# fpga02-serdes-power.net
KiCad netlist of a schematic drawn in Altium Designer
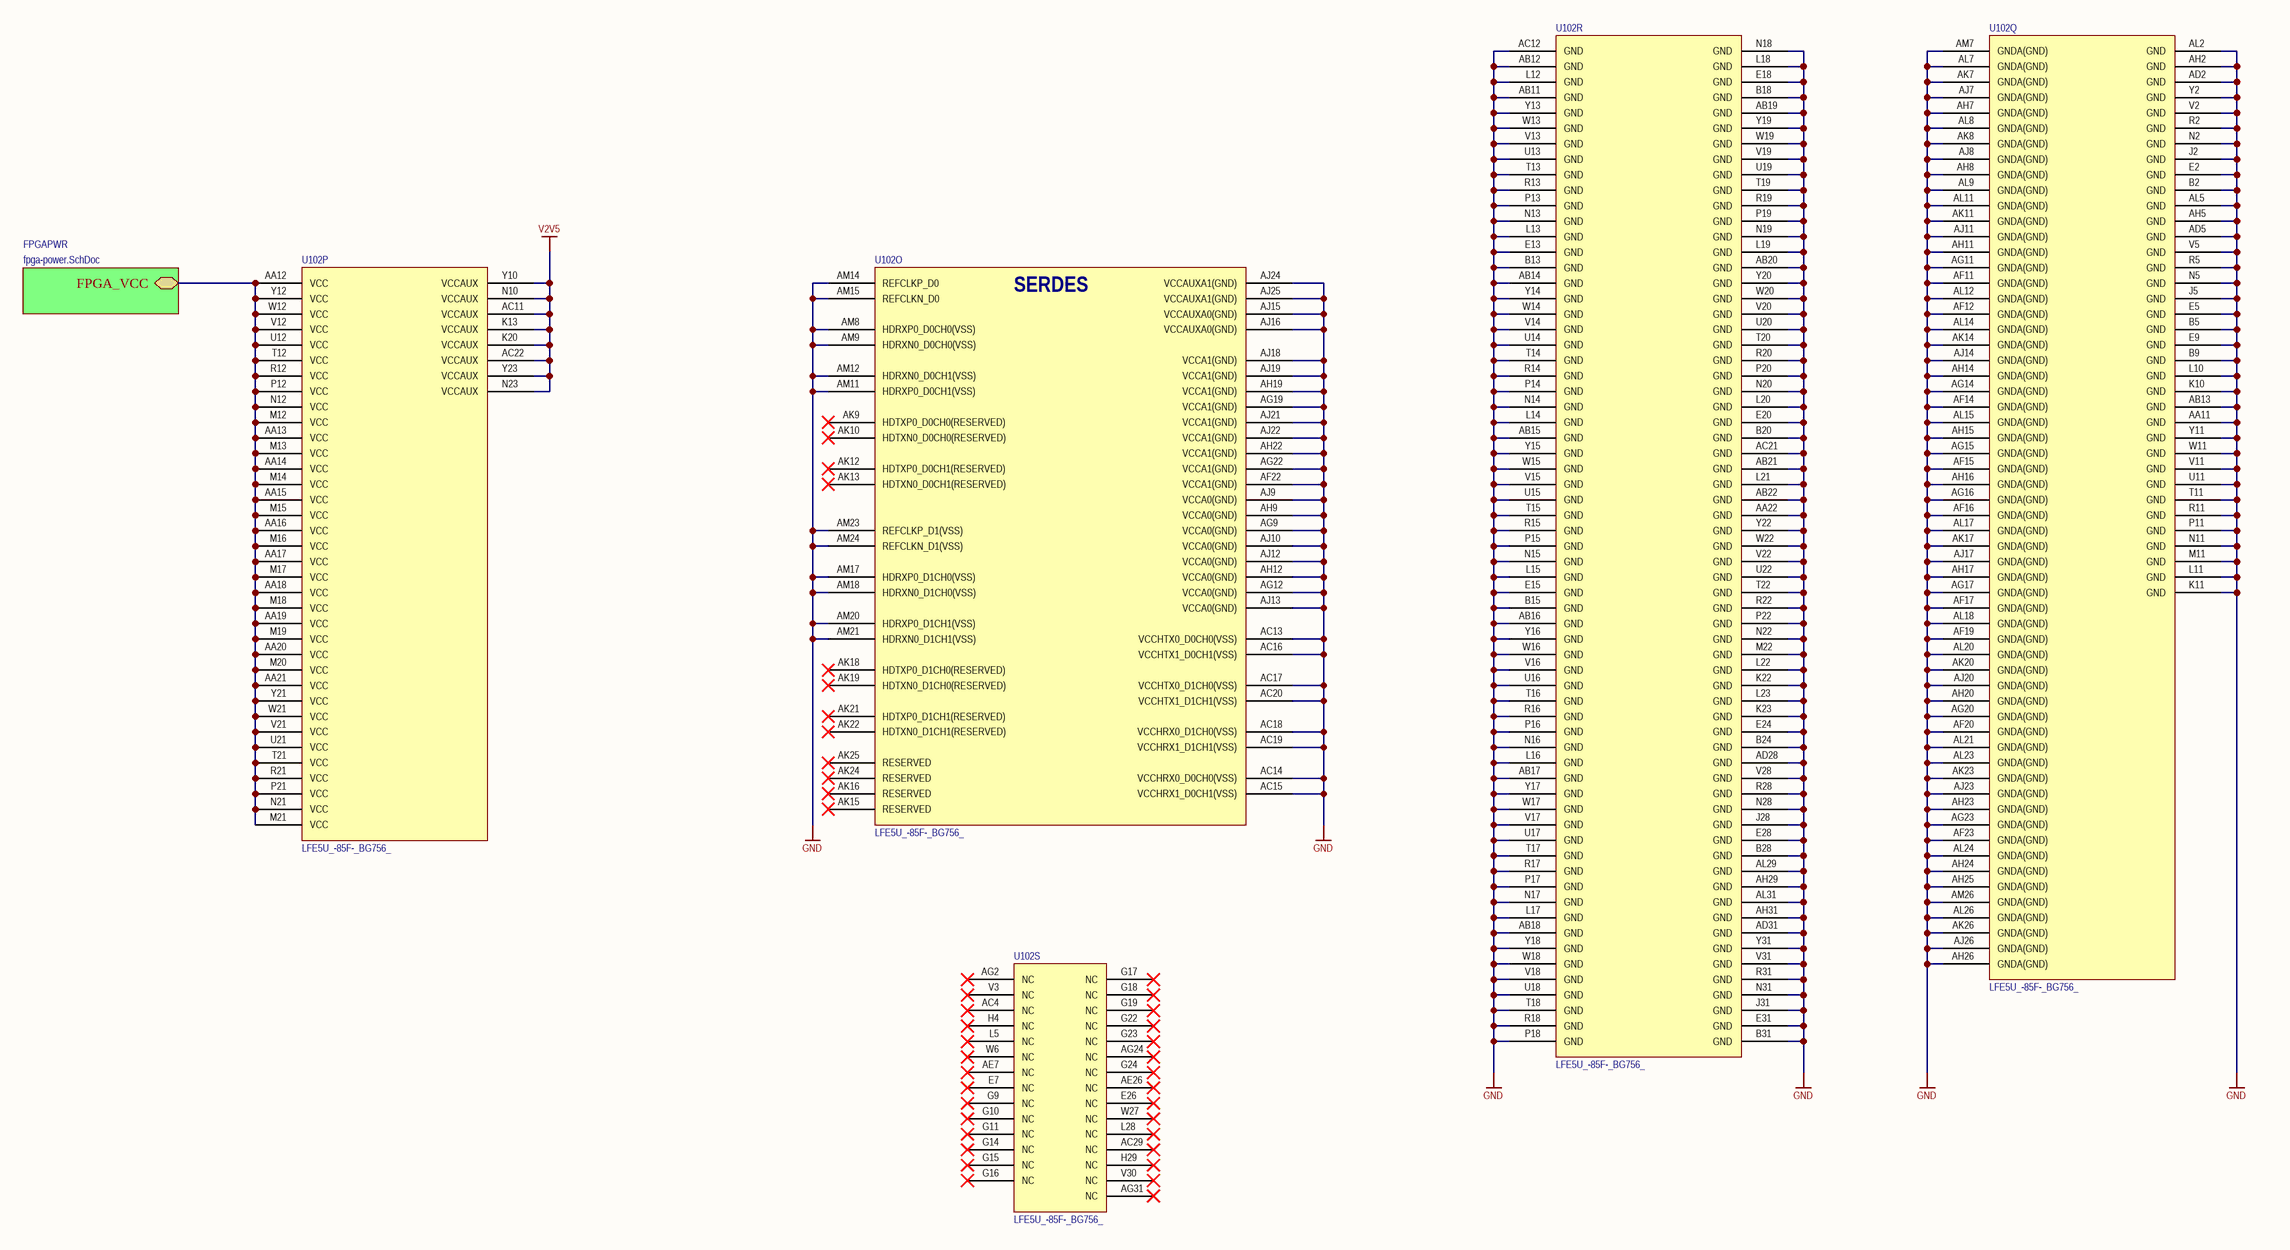
[diagram p0: fpga02-serdes-power.SchDoc]

(export (version "E")
  (design (tool "Eeschema 10.0.6"))
  (components
    (comp (ref "U102")
      (value "LFE5U_-85F-_BG756_")
      (footprint "lattice:caBGA756")
      (description "ECP5 FPGA, 85k LUT, 756-caBGA")
      (fields (field (name "MANUFACTURER") "Lattice Semiconductor"))
      (libsource (lib "lattice") (part "LFE5U_-85F-_BG756_"))
    )
  )
  (nets
    (net (code "1") (name "/FPGA_VCC") (class "Default")
      (node (ref "U102") (pin "AA12") (pinfunction "VCC_AA12") (pintype "power_in"))
      (node (ref "U102") (pin "AA13") (pinfunction "VCC_AA13") (pintype "power_in"))
      (node (ref "U102") (pin "AA14") (pinfunction "VCC_AA14") (pintype "power_in"))
      (node (ref "U102") (pin "AA15") (pinfunction "VCC_AA15") (pintype "power_in"))
      (node (ref "U102") (pin "AA16") (pinfunction "VCC_AA16") (pintype "power_in"))
      (node (ref "U102") (pin "AA17") (pinfunction "VCC_AA17") (pintype "power_in"))
      (node (ref "U102") (pin "AA18") (pinfunction "VCC_AA18") (pintype "power_in"))
      (node (ref "U102") (pin "AA19") (pinfunction "VCC_AA19") (pintype "power_in"))
      (node (ref "U102") (pin "AA20") (pinfunction "VCC_AA20") (pintype "power_in"))
      (node (ref "U102") (pin "AA21") (pinfunction "VCC_AA21") (pintype "power_in"))
      (node (ref "U102") (pin "M12") (pinfunction "VCC_M12") (pintype "power_in"))
      (node (ref "U102") (pin "M13") (pinfunction "VCC_M13") (pintype "power_in"))
      (node (ref "U102") (pin "M14") (pinfunction "VCC_M14") (pintype "power_in"))
      (node (ref "U102") (pin "M15") (pinfunction "VCC_M15") (pintype "power_in"))
      (node (ref "U102") (pin "M16") (pinfunction "VCC_M16") (pintype "power_in"))
      (node (ref "U102") (pin "M17") (pinfunction "VCC_M17") (pintype "power_in"))
      (node (ref "U102") (pin "M18") (pinfunction "VCC_M18") (pintype "power_in"))
      (node (ref "U102") (pin "M19") (pinfunction "VCC_M19") (pintype "power_in"))
      (node (ref "U102") (pin "M20") (pinfunction "VCC_M20") (pintype "power_in"))
      (node (ref "U102") (pin "M21") (pinfunction "VCC_M21") (pintype "power_in"))
      (node (ref "U102") (pin "N12") (pinfunction "VCC_N12") (pintype "power_in"))
      (node (ref "U102") (pin "N21") (pinfunction "VCC_N21") (pintype "power_in"))
      (node (ref "U102") (pin "P12") (pinfunction "VCC_P12") (pintype "power_in"))
      (node (ref "U102") (pin "P21") (pinfunction "VCC_P21") (pintype "power_in"))
      (node (ref "U102") (pin "R12") (pinfunction "VCC_R12") (pintype "power_in"))
      (node (ref "U102") (pin "R21") (pinfunction "VCC_R21") (pintype "power_in"))
      (node (ref "U102") (pin "T12") (pinfunction "VCC_T12") (pintype "power_in"))
      (node (ref "U102") (pin "T21") (pinfunction "VCC_T21") (pintype "power_in"))
      (node (ref "U102") (pin "U12") (pinfunction "VCC_U12") (pintype "power_in"))
      (node (ref "U102") (pin "U21") (pinfunction "VCC_U21") (pintype "power_in"))
      (node (ref "U102") (pin "V12") (pinfunction "VCC_V12") (pintype "power_in"))
      (node (ref "U102") (pin "V21") (pinfunction "VCC_V21") (pintype "power_in"))
      (node (ref "U102") (pin "W12") (pinfunction "VCC_W12") (pintype "power_in"))
      (node (ref "U102") (pin "W21") (pinfunction "VCC_W21") (pintype "power_in"))
      (node (ref "U102") (pin "Y12") (pinfunction "VCC_Y12") (pintype "power_in"))
      (node (ref "U102") (pin "Y21") (pinfunction "VCC_Y21") (pintype "power_in"))
    )
    (net (code "2") (name "GND") (class "Default")
      (node (ref "U102") (pin "AA11") (pinfunction "GND_AA11") (pintype "power_in"))
      (node (ref "U102") (pin "AA22") (pinfunction "GND_AA22") (pintype "power_in"))
      (node (ref "U102") (pin "AB11") (pinfunction "GND_AB11") (pintype "power_in"))
      (node (ref "U102") (pin "AB12") (pinfunction "GND_AB12") (pintype "power_in"))
      (node (ref "U102") (pin "AB13") (pinfunction "GND_AB13") (pintype "power_in"))
      (node (ref "U102") (pin "AB14") (pinfunction "GND_AB14") (pintype "power_in"))
      (node (ref "U102") (pin "AB15") (pinfunction "GND_AB15") (pintype "power_in"))
      (node (ref "U102") (pin "AB16") (pinfunction "GND_AB16") (pintype "power_in"))
      (node (ref "U102") (pin "AB17") (pinfunction "GND_AB17") (pintype "power_in"))
      (node (ref "U102") (pin "AB18") (pinfunction "GND_AB18") (pintype "power_in"))
      (node (ref "U102") (pin "AB19") (pinfunction "GND_AB19") (pintype "power_in"))
      (node (ref "U102") (pin "AB20") (pinfunction "GND_AB20") (pintype "power_in"))
      (node (ref "U102") (pin "AB21") (pinfunction "GND_AB21") (pintype "power_in"))
      (node (ref "U102") (pin "AB22") (pinfunction "GND_AB22") (pintype "power_in"))
      (node (ref "U102") (pin "AC12") (pinfunction "GND_AC12") (pintype "power_in"))
      (node (ref "U102") (pin "AC13") (pinfunction "VCCHTX0_D0CH0(VSS)_AC13") (pintype "power_in"))
      (node (ref "U102") (pin "AC14") (pinfunction "VCCHRX0_D0CH0(VSS)_AC14") (pintype "power_in"))
      (node (ref "U102") (pin "AC15") (pinfunction "VCCHRX1_D0CH1(VSS)_AC15") (pintype "power_in"))
      (node (ref "U102") (pin "AC16") (pinfunction "VCCHTX1_D0CH1(VSS)_AC16") (pintype "power_in"))
      (node (ref "U102") (pin "AC17") (pinfunction "VCCHTX0_D1CH0(VSS)_AC17") (pintype "power_in"))
      (node (ref "U102") (pin "AC18") (pinfunction "VCCHRX0_D1CH0(VSS)_AC18") (pintype "power_in"))
      (node (ref "U102") (pin "AC19") (pinfunction "VCCHRX1_D1CH1(VSS)_AC19") (pintype "power_in"))
      (node (ref "U102") (pin "AC20") (pinfunction "VCCHTX1_D1CH1(VSS)_AC20") (pintype "power_in"))
      (node (ref "U102") (pin "AC21") (pinfunction "GND_AC21") (pintype "power_in"))
      (node (ref "U102") (pin "AD2") (pinfunction "GND_AD2") (pintype "power_in"))
      (node (ref "U102") (pin "AD28") (pinfunction "GND_AD28") (pintype "power_in"))
      (node (ref "U102") (pin "AD31") (pinfunction "GND_AD31") (pintype "power_in"))
      (node (ref "U102") (pin "AD5") (pinfunction "GND_AD5") (pintype "power_in"))
      (node (ref "U102") (pin "AF11") (pinfunction "GNDA(GND)_AF11") (pintype "power_in"))
      (node (ref "U102") (pin "AF12") (pinfunction "GNDA(GND)_AF12") (pintype "power_in"))
      (node (ref "U102") (pin "AF14") (pinfunction "GNDA(GND)_AF14") (pintype "power_in"))
      (node (ref "U102") (pin "AF15") (pinfunction "GNDA(GND)_AF15") (pintype "power_in"))
      (node (ref "U102") (pin "AF16") (pinfunction "GNDA(GND)_AF16") (pintype "power_in"))
      (node (ref "U102") (pin "AF17") (pinfunction "GNDA(GND)_AF17") (pintype "power_in"))
      (node (ref "U102") (pin "AF19") (pinfunction "GNDA(GND)_AF19") (pintype "power_in"))
      (node (ref "U102") (pin "AF20") (pinfunction "GNDA(GND)_AF20") (pintype "power_in"))
      (node (ref "U102") (pin "AF22") (pinfunction "VCCA1(GND)_AF22") (pintype "power_in"))
      (node (ref "U102") (pin "AF23") (pinfunction "GNDA(GND)_AF23") (pintype "power_in"))
      (node (ref "U102") (pin "AG11") (pinfunction "GNDA(GND)_AG11") (pintype "power_in"))
      (node (ref "U102") (pin "AG12") (pinfunction "VCCA0(GND)_AG12") (pintype "power_in"))
      (node (ref "U102") (pin "AG14") (pinfunction "GNDA(GND)_AG14") (pintype "power_in"))
      (node (ref "U102") (pin "AG15") (pinfunction "GNDA(GND)_AG15") (pintype "power_in"))
      (node (ref "U102") (pin "AG16") (pinfunction "GNDA(GND)_AG16") (pintype "power_in"))
      (node (ref "U102") (pin "AG17") (pinfunction "GNDA(GND)_AG17") (pintype "power_in"))
      (node (ref "U102") (pin "AG19") (pinfunction "VCCA1(GND)_AG19") (pintype "power_in"))
      (node (ref "U102") (pin "AG20") (pinfunction "GNDA(GND)_AG20") (pintype "power_in"))
      (node (ref "U102") (pin "AG22") (pinfunction "VCCA1(GND)_AG22") (pintype "power_in"))
      (node (ref "U102") (pin "AG23") (pinfunction "GNDA(GND)_AG23") (pintype "power_in"))
      (node (ref "U102") (pin "AG9") (pinfunction "VCCA0(GND)_AG9") (pintype "power_in"))
      (node (ref "U102") (pin "AH11") (pinfunction "GNDA(GND)_AH11") (pintype "power_in"))
      (node (ref "U102") (pin "AH12") (pinfunction "VCCA0(GND)_AH12") (pintype "power_in"))
      (node (ref "U102") (pin "AH14") (pinfunction "GNDA(GND)_AH14") (pintype "power_in"))
      (node (ref "U102") (pin "AH15") (pinfunction "GNDA(GND)_AH15") (pintype "power_in"))
      (node (ref "U102") (pin "AH16") (pinfunction "GNDA(GND)_AH16") (pintype "power_in"))
      (node (ref "U102") (pin "AH17") (pinfunction "GNDA(GND)_AH17") (pintype "power_in"))
      (node (ref "U102") (pin "AH19") (pinfunction "VCCA1(GND)_AH19") (pintype "power_in"))
      (node (ref "U102") (pin "AH2") (pinfunction "GND_AH2") (pintype "power_in"))
      (node (ref "U102") (pin "AH20") (pinfunction "GNDA(GND)_AH20") (pintype "power_in"))
      (node (ref "U102") (pin "AH22") (pinfunction "VCCA1(GND)_AH22") (pintype "power_in"))
      (node (ref "U102") (pin "AH23") (pinfunction "GNDA(GND)_AH23") (pintype "power_in"))
      (node (ref "U102") (pin "AH24") (pinfunction "GNDA(GND)_AH24") (pintype "power_in"))
      (node (ref "U102") (pin "AH25") (pinfunction "GNDA(GND)_AH25") (pintype "power_in"))
      (node (ref "U102") (pin "AH26") (pinfunction "GNDA(GND)_AH26") (pintype "power_in"))
      (node (ref "U102") (pin "AH29") (pinfunction "GND_AH29") (pintype "power_in"))
      (node (ref "U102") (pin "AH31") (pinfunction "GND_AH31") (pintype "power_in"))
      (node (ref "U102") (pin "AH5") (pinfunction "GND_AH5") (pintype "power_in"))
      (node (ref "U102") (pin "AH7") (pinfunction "GNDA(GND)_AH7") (pintype "power_in"))
      (node (ref "U102") (pin "AH8") (pinfunction "GNDA(GND)_AH8") (pintype "power_in"))
      (node (ref "U102") (pin "AH9") (pinfunction "VCCA0(GND)_AH9") (pintype "power_in"))
      (node (ref "U102") (pin "AJ10") (pinfunction "VCCA0(GND)_AJ10") (pintype "power_in"))
      (node (ref "U102") (pin "AJ11") (pinfunction "GNDA(GND)_AJ11") (pintype "power_in"))
      (node (ref "U102") (pin "AJ12") (pinfunction "VCCA0(GND)_AJ12") (pintype "power_in"))
      (node (ref "U102") (pin "AJ13") (pinfunction "VCCA0(GND)_AJ13") (pintype "power_in"))
      (node (ref "U102") (pin "AJ14") (pinfunction "GNDA(GND)_AJ14") (pintype "power_in"))
      (node (ref "U102") (pin "AJ15") (pinfunction "VCCAUXA0(GND)_AJ15") (pintype "power_in"))
      (node (ref "U102") (pin "AJ16") (pinfunction "VCCAUXA0(GND)_AJ16") (pintype "power_in"))
      (node (ref "U102") (pin "AJ17") (pinfunction "GNDA(GND)_AJ17") (pintype "power_in"))
      (node (ref "U102") (pin "AJ18") (pinfunction "VCCA1(GND)_AJ18") (pintype "power_in"))
      (node (ref "U102") (pin "AJ19") (pinfunction "VCCA1(GND)_AJ19") (pintype "power_in"))
      (node (ref "U102") (pin "AJ20") (pinfunction "GNDA(GND)_AJ20") (pintype "power_in"))
      (node (ref "U102") (pin "AJ21") (pinfunction "VCCA1(GND)_AJ21") (pintype "power_in"))
      (node (ref "U102") (pin "AJ22") (pinfunction "VCCA1(GND)_AJ22") (pintype "power_in"))
      (node (ref "U102") (pin "AJ23") (pinfunction "GNDA(GND)_AJ23") (pintype "power_in"))
      (node (ref "U102") (pin "AJ24") (pinfunction "VCCAUXA1(GND)_AJ24") (pintype "power_in"))
      (node (ref "U102") (pin "AJ25") (pinfunction "VCCAUXA1(GND)_AJ25") (pintype "power_in"))
      (node (ref "U102") (pin "AJ26") (pinfunction "GNDA(GND)_AJ26") (pintype "power_in"))
      (node (ref "U102") (pin "AJ7") (pinfunction "GNDA(GND)_AJ7") (pintype "power_in"))
      (node (ref "U102") (pin "AJ8") (pinfunction "GNDA(GND)_AJ8") (pintype "power_in"))
      (node (ref "U102") (pin "AJ9") (pinfunction "VCCA0(GND)_AJ9") (pintype "power_in"))
      (node (ref "U102") (pin "AK11") (pinfunction "GNDA(GND)_AK11") (pintype "power_in"))
      (node (ref "U102") (pin "AK14") (pinfunction "GNDA(GND)_AK14") (pintype "power_in"))
      (node (ref "U102") (pin "AK17") (pinfunction "GNDA(GND)_AK17") (pintype "power_in"))
      (node (ref "U102") (pin "AK20") (pinfunction "GNDA(GND)_AK20") (pintype "power_in"))
      (node (ref "U102") (pin "AK23") (pinfunction "GNDA(GND)_AK23") (pintype "power_in"))
      (node (ref "U102") (pin "AK26") (pinfunction "GNDA(GND)_AK26") (pintype "power_in"))
      (node (ref "U102") (pin "AK7") (pinfunction "GNDA(GND)_AK7") (pintype "power_in"))
      (node (ref "U102") (pin "AK8") (pinfunction "GNDA(GND)_AK8") (pintype "power_in"))
      (node (ref "U102") (pin "AL11") (pinfunction "GNDA(GND)_AL11") (pintype "power_in"))
      (node (ref "U102") (pin "AL12") (pinfunction "GNDA(GND)_AL12") (pintype "power_in"))
      (node (ref "U102") (pin "AL14") (pinfunction "GNDA(GND)_AL14") (pintype "power_in"))
      (node (ref "U102") (pin "AL15") (pinfunction "GNDA(GND)_AL15") (pintype "power_in"))
      (node (ref "U102") (pin "AL17") (pinfunction "GNDA(GND)_AL17") (pintype "power_in"))
      (node (ref "U102") (pin "AL18") (pinfunction "GNDA(GND)_AL18") (pintype "power_in"))
      (node (ref "U102") (pin "AL2") (pinfunction "GND_AL2") (pintype "power_in"))
      (node (ref "U102") (pin "AL20") (pinfunction "GNDA(GND)_AL20") (pintype "power_in"))
      (node (ref "U102") (pin "AL21") (pinfunction "GNDA(GND)_AL21") (pintype "power_in"))
      (node (ref "U102") (pin "AL23") (pinfunction "GNDA(GND)_AL23") (pintype "power_in"))
      (node (ref "U102") (pin "AL24") (pinfunction "GNDA(GND)_AL24") (pintype "power_in"))
      (node (ref "U102") (pin "AL26") (pinfunction "GNDA(GND)_AL26") (pintype "power_in"))
      (node (ref "U102") (pin "AL29") (pinfunction "GND_AL29") (pintype "power_in"))
      (node (ref "U102") (pin "AL31") (pinfunction "GND_AL31") (pintype "power_in"))
      (node (ref "U102") (pin "AL5") (pinfunction "GND_AL5") (pintype "power_in"))
      (node (ref "U102") (pin "AL7") (pinfunction "GNDA(GND)_AL7") (pintype "power_in"))
      (node (ref "U102") (pin "AL8") (pinfunction "GNDA(GND)_AL8") (pintype "power_in"))
      (node (ref "U102") (pin "AL9") (pinfunction "GNDA(GND)_AL9") (pintype "power_in"))
      (node (ref "U102") (pin "AM11") (pinfunction "HDRXP0_D0CH1(VSS)_AM11") (pintype "passive"))
      (node (ref "U102") (pin "AM12") (pinfunction "HDRXN0_D0CH1(VSS)_AM12") (pintype "passive"))
      (node (ref "U102") (pin "AM14") (pinfunction "REFCLKP_D0_AM14") (pintype "passive"))
      (node (ref "U102") (pin "AM15") (pinfunction "REFCLKN_D0_AM15") (pintype "passive"))
      (node (ref "U102") (pin "AM17") (pinfunction "HDRXP0_D1CH0(VSS)_AM17") (pintype "passive"))
      (node (ref "U102") (pin "AM18") (pinfunction "HDRXN0_D1CH0(VSS)_AM18") (pintype "passive"))
      (node (ref "U102") (pin "AM20") (pinfunction "HDRXP0_D1CH1(VSS)_AM20") (pintype "passive"))
      (node (ref "U102") (pin "AM21") (pinfunction "HDRXN0_D1CH1(VSS)_AM21") (pintype "passive"))
      (node (ref "U102") (pin "AM23") (pinfunction "REFCLKP_D1(VSS)_AM23") (pintype "passive"))
      (node (ref "U102") (pin "AM24") (pinfunction "REFCLKN_D1(VSS)_AM24") (pintype "passive"))
      (node (ref "U102") (pin "AM26") (pinfunction "GNDA(GND)_AM26") (pintype "power_in"))
      (node (ref "U102") (pin "AM7") (pinfunction "GNDA(GND)_AM7") (pintype "power_in"))
      (node (ref "U102") (pin "AM8") (pinfunction "HDRXP0_D0CH0(VSS)_AM8") (pintype "passive"))
      (node (ref "U102") (pin "AM9") (pinfunction "HDRXN0_D0CH0(VSS)_AM9") (pintype "passive"))
      (node (ref "U102") (pin "B13") (pinfunction "GND_B13") (pintype "power_in"))
      (node (ref "U102") (pin "B15") (pinfunction "GND_B15") (pintype "power_in"))
      (node (ref "U102") (pin "B18") (pinfunction "GND_B18") (pintype "power_in"))
      (node (ref "U102") (pin "B2") (pinfunction "GND_B2") (pintype "power_in"))
      (node (ref "U102") (pin "B20") (pinfunction "GND_B20") (pintype "power_in"))
      (node (ref "U102") (pin "B24") (pinfunction "GND_B24") (pintype "power_in"))
      (node (ref "U102") (pin "B28") (pinfunction "GND_B28") (pintype "power_in"))
      (node (ref "U102") (pin "B31") (pinfunction "GND_B31") (pintype "power_in"))
      (node (ref "U102") (pin "B5") (pinfunction "GND_B5") (pintype "power_in"))
      (node (ref "U102") (pin "B9") (pinfunction "GND_B9") (pintype "power_in"))
      (node (ref "U102") (pin "E13") (pinfunction "GND_E13") (pintype "power_in"))
      (node (ref "U102") (pin "E15") (pinfunction "GND_E15") (pintype "power_in"))
      (node (ref "U102") (pin "E18") (pinfunction "GND_E18") (pintype "power_in"))
      (node (ref "U102") (pin "E2") (pinfunction "GND_E2") (pintype "power_in"))
      (node (ref "U102") (pin "E20") (pinfunction "GND_E20") (pintype "power_in"))
      (node (ref "U102") (pin "E24") (pinfunction "GND_E24") (pintype "power_in"))
      (node (ref "U102") (pin "E28") (pinfunction "GND_E28") (pintype "power_in"))
      (node (ref "U102") (pin "E31") (pinfunction "GND_E31") (pintype "power_in"))
      (node (ref "U102") (pin "E5") (pinfunction "GND_E5") (pintype "power_in"))
      (node (ref "U102") (pin "E9") (pinfunction "GND_E9") (pintype "power_in"))
      (node (ref "U102") (pin "J2") (pinfunction "GND_J2") (pintype "power_in"))
      (node (ref "U102") (pin "J28") (pinfunction "GND_J28") (pintype "power_in"))
      (node (ref "U102") (pin "J31") (pinfunction "GND_J31") (pintype "power_in"))
      (node (ref "U102") (pin "J5") (pinfunction "GND_J5") (pintype "power_in"))
      (node (ref "U102") (pin "K10") (pinfunction "GND_K10") (pintype "power_in"))
      (node (ref "U102") (pin "K11") (pinfunction "GND_K11") (pintype "power_in"))
      (node (ref "U102") (pin "K22") (pinfunction "GND_K22") (pintype "power_in"))
      (node (ref "U102") (pin "K23") (pinfunction "GND_K23") (pintype "power_in"))
      (node (ref "U102") (pin "L10") (pinfunction "GND_L10") (pintype "power_in"))
      (node (ref "U102") (pin "L11") (pinfunction "GND_L11") (pintype "power_in"))
      (node (ref "U102") (pin "L12") (pinfunction "GND_L12") (pintype "power_in"))
      (node (ref "U102") (pin "L13") (pinfunction "GND_L13") (pintype "power_in"))
      (node (ref "U102") (pin "L14") (pinfunction "GND_L14") (pintype "power_in"))
      (node (ref "U102") (pin "L15") (pinfunction "GND_L15") (pintype "power_in"))
      (node (ref "U102") (pin "L16") (pinfunction "GND_L16") (pintype "power_in"))
      (node (ref "U102") (pin "L17") (pinfunction "GND_L17") (pintype "power_in"))
      (node (ref "U102") (pin "L18") (pinfunction "GND_L18") (pintype "power_in"))
      (node (ref "U102") (pin "L19") (pinfunction "GND_L19") (pintype "power_in"))
      (node (ref "U102") (pin "L20") (pinfunction "GND_L20") (pintype "power_in"))
      (node (ref "U102") (pin "L21") (pinfunction "GND_L21") (pintype "power_in"))
      (node (ref "U102") (pin "L22") (pinfunction "GND_L22") (pintype "power_in"))
      (node (ref "U102") (pin "L23") (pinfunction "GND_L23") (pintype "power_in"))
      (node (ref "U102") (pin "M11") (pinfunction "GND_M11") (pintype "power_in"))
      (node (ref "U102") (pin "M22") (pinfunction "GND_M22") (pintype "power_in"))
      (node (ref "U102") (pin "N11") (pinfunction "GND_N11") (pintype "power_in"))
      (node (ref "U102") (pin "N13") (pinfunction "GND_N13") (pintype "power_in"))
      (node (ref "U102") (pin "N14") (pinfunction "GND_N14") (pintype "power_in"))
      (node (ref "U102") (pin "N15") (pinfunction "GND_N15") (pintype "power_in"))
      (node (ref "U102") (pin "N16") (pinfunction "GND_N16") (pintype "power_in"))
      (node (ref "U102") (pin "N17") (pinfunction "GND_N17") (pintype "power_in"))
      (node (ref "U102") (pin "N18") (pinfunction "GND_N18") (pintype "power_in"))
      (node (ref "U102") (pin "N19") (pinfunction "GND_N19") (pintype "power_in"))
      (node (ref "U102") (pin "N2") (pinfunction "GND_N2") (pintype "power_in"))
      (node (ref "U102") (pin "N20") (pinfunction "GND_N20") (pintype "power_in"))
      (node (ref "U102") (pin "N22") (pinfunction "GND_N22") (pintype "power_in"))
      (node (ref "U102") (pin "N28") (pinfunction "GND_N28") (pintype "power_in"))
      (node (ref "U102") (pin "N31") (pinfunction "GND_N31") (pintype "power_in"))
      (node (ref "U102") (pin "N5") (pinfunction "GND_N5") (pintype "power_in"))
      (node (ref "U102") (pin "P11") (pinfunction "GND_P11") (pintype "power_in"))
      (node (ref "U102") (pin "P13") (pinfunction "GND_P13") (pintype "power_in"))
      (node (ref "U102") (pin "P14") (pinfunction "GND_P14") (pintype "power_in"))
      (node (ref "U102") (pin "P15") (pinfunction "GND_P15") (pintype "power_in"))
      (node (ref "U102") (pin "P16") (pinfunction "GND_P16") (pintype "power_in"))
      (node (ref "U102") (pin "P17") (pinfunction "GND_P17") (pintype "power_in"))
      (node (ref "U102") (pin "P18") (pinfunction "GND_P18") (pintype "power_in"))
      (node (ref "U102") (pin "P19") (pinfunction "GND_P19") (pintype "power_in"))
      (node (ref "U102") (pin "P20") (pinfunction "GND_P20") (pintype "power_in"))
      (node (ref "U102") (pin "P22") (pinfunction "GND_P22") (pintype "power_in"))
      (node (ref "U102") (pin "R11") (pinfunction "GND_R11") (pintype "power_in"))
      (node (ref "U102") (pin "R13") (pinfunction "GND_R13") (pintype "power_in"))
      (node (ref "U102") (pin "R14") (pinfunction "GND_R14") (pintype "power_in"))
      (node (ref "U102") (pin "R15") (pinfunction "GND_R15") (pintype "power_in"))
      (node (ref "U102") (pin "R16") (pinfunction "GND_R16") (pintype "power_in"))
      (node (ref "U102") (pin "R17") (pinfunction "GND_R17") (pintype "power_in"))
      (node (ref "U102") (pin "R18") (pinfunction "GND_R18") (pintype "power_in"))
      (node (ref "U102") (pin "R19") (pinfunction "GND_R19") (pintype "power_in"))
      (node (ref "U102") (pin "R2") (pinfunction "GND_R2") (pintype "power_in"))
      (node (ref "U102") (pin "R20") (pinfunction "GND_R20") (pintype "power_in"))
      (node (ref "U102") (pin "R22") (pinfunction "GND_R22") (pintype "power_in"))
      (node (ref "U102") (pin "R28") (pinfunction "GND_R28") (pintype "power_in"))
      (node (ref "U102") (pin "R31") (pinfunction "GND_R31") (pintype "power_in"))
      (node (ref "U102") (pin "R5") (pinfunction "GND_R5") (pintype "power_in"))
      (node (ref "U102") (pin "T11") (pinfunction "GND_T11") (pintype "power_in"))
      (node (ref "U102") (pin "T13") (pinfunction "GND_T13") (pintype "power_in"))
      (node (ref "U102") (pin "T14") (pinfunction "GND_T14") (pintype "power_in"))
      (node (ref "U102") (pin "T15") (pinfunction "GND_T15") (pintype "power_in"))
      (node (ref "U102") (pin "T16") (pinfunction "GND_T16") (pintype "power_in"))
      (node (ref "U102") (pin "T17") (pinfunction "GND_T17") (pintype "power_in"))
      (node (ref "U102") (pin "T18") (pinfunction "GND_T18") (pintype "power_in"))
      (node (ref "U102") (pin "T19") (pinfunction "GND_T19") (pintype "power_in"))
      (node (ref "U102") (pin "T20") (pinfunction "GND_T20") (pintype "power_in"))
      (node (ref "U102") (pin "T22") (pinfunction "GND_T22") (pintype "power_in"))
      (node (ref "U102") (pin "U11") (pinfunction "GND_U11") (pintype "power_in"))
      (node (ref "U102") (pin "U13") (pinfunction "GND_U13") (pintype "power_in"))
      (node (ref "U102") (pin "U14") (pinfunction "GND_U14") (pintype "power_in"))
      (node (ref "U102") (pin "U15") (pinfunction "GND_U15") (pintype "power_in"))
      (node (ref "U102") (pin "U16") (pinfunction "GND_U16") (pintype "power_in"))
      (node (ref "U102") (pin "U17") (pinfunction "GND_U17") (pintype "power_in"))
      (node (ref "U102") (pin "U18") (pinfunction "GND_U18") (pintype "power_in"))
      (node (ref "U102") (pin "U19") (pinfunction "GND_U19") (pintype "power_in"))
      (node (ref "U102") (pin "U20") (pinfunction "GND_U20") (pintype "power_in"))
      (node (ref "U102") (pin "U22") (pinfunction "GND_U22") (pintype "power_in"))
      (node (ref "U102") (pin "V11") (pinfunction "GND_V11") (pintype "power_in"))
      (node (ref "U102") (pin "V13") (pinfunction "GND_V13") (pintype "power_in"))
      (node (ref "U102") (pin "V14") (pinfunction "GND_V14") (pintype "power_in"))
      (node (ref "U102") (pin "V15") (pinfunction "GND_V15") (pintype "power_in"))
      (node (ref "U102") (pin "V16") (pinfunction "GND_V16") (pintype "power_in"))
      (node (ref "U102") (pin "V17") (pinfunction "GND_V17") (pintype "power_in"))
      (node (ref "U102") (pin "V18") (pinfunction "GND_V18") (pintype "power_in"))
      (node (ref "U102") (pin "V19") (pinfunction "GND_V19") (pintype "power_in"))
      (node (ref "U102") (pin "V2") (pinfunction "GND_V2") (pintype "power_in"))
      (node (ref "U102") (pin "V20") (pinfunction "GND_V20") (pintype "power_in"))
      (node (ref "U102") (pin "V22") (pinfunction "GND_V22") (pintype "power_in"))
      (node (ref "U102") (pin "V28") (pinfunction "GND_V28") (pintype "power_in"))
      (node (ref "U102") (pin "V31") (pinfunction "GND_V31") (pintype "power_in"))
      (node (ref "U102") (pin "V5") (pinfunction "GND_V5") (pintype "power_in"))
      (node (ref "U102") (pin "W11") (pinfunction "GND_W11") (pintype "power_in"))
      (node (ref "U102") (pin "W13") (pinfunction "GND_W13") (pintype "power_in"))
      (node (ref "U102") (pin "W14") (pinfunction "GND_W14") (pintype "power_in"))
      (node (ref "U102") (pin "W15") (pinfunction "GND_W15") (pintype "power_in"))
      (node (ref "U102") (pin "W16") (pinfunction "GND_W16") (pintype "power_in"))
      (node (ref "U102") (pin "W17") (pinfunction "GND_W17") (pintype "power_in"))
      (node (ref "U102") (pin "W18") (pinfunction "GND_W18") (pintype "power_in"))
      (node (ref "U102") (pin "W19") (pinfunction "GND_W19") (pintype "power_in"))
      (node (ref "U102") (pin "W20") (pinfunction "GND_W20") (pintype "power_in"))
      (node (ref "U102") (pin "W22") (pinfunction "GND_W22") (pintype "power_in"))
      (node (ref "U102") (pin "Y11") (pinfunction "GND_Y11") (pintype "power_in"))
      (node (ref "U102") (pin "Y13") (pinfunction "GND_Y13") (pintype "power_in"))
      (node (ref "U102") (pin "Y14") (pinfunction "GND_Y14") (pintype "power_in"))
      (node (ref "U102") (pin "Y15") (pinfunction "GND_Y15") (pintype "power_in"))
      (node (ref "U102") (pin "Y16") (pinfunction "GND_Y16") (pintype "power_in"))
      (node (ref "U102") (pin "Y17") (pinfunction "GND_Y17") (pintype "power_in"))
      (node (ref "U102") (pin "Y18") (pinfunction "GND_Y18") (pintype "power_in"))
      (node (ref "U102") (pin "Y19") (pinfunction "GND_Y19") (pintype "power_in"))
      (node (ref "U102") (pin "Y2") (pinfunction "GND_Y2") (pintype "power_in"))
      (node (ref "U102") (pin "Y20") (pinfunction "GND_Y20") (pintype "power_in"))
      (node (ref "U102") (pin "Y22") (pinfunction "GND_Y22") (pintype "power_in"))
      (node (ref "U102") (pin "Y31") (pinfunction "GND_Y31") (pintype "power_in"))
    )
    (net (code "3") (name "V2V5") (class "Default")
      (node (ref "U102") (pin "AC11") (pinfunction "VCCAUX_AC11") (pintype "power_in"))
      (node (ref "U102") (pin "AC22") (pinfunction "VCCAUX_AC22") (pintype "power_in"))
      (node (ref "U102") (pin "K13") (pinfunction "VCCAUX_K13") (pintype "power_in"))
      (node (ref "U102") (pin "K20") (pinfunction "VCCAUX_K20") (pintype "power_in"))
      (node (ref "U102") (pin "N10") (pinfunction "VCCAUX_N10") (pintype "power_in"))
      (node (ref "U102") (pin "N23") (pinfunction "VCCAUX_N23") (pintype "power_in"))
      (node (ref "U102") (pin "Y10") (pinfunction "VCCAUX_Y10") (pintype "power_in"))
      (node (ref "U102") (pin "Y23") (pinfunction "VCCAUX_Y23") (pintype "power_in"))
    )
    (net (code "4") (name "unconnected-(U102O-HDTXN0_D0CH0(RESERVED)-PadAK10)") (class "Default")
      (node (ref "U102") (pin "AK10") (pinfunction "HDTXN0_D0CH0(RESERVED)_AK10") (pintype "passive+no_connect"))
    )
    (net (code "5") (name "unconnected-(U102O-HDTXN0_D0CH1(RESERVED)-PadAK13)") (class "Default")
      (node (ref "U102") (pin "AK13") (pinfunction "HDTXN0_D0CH1(RESERVED)_AK13") (pintype "passive+no_connect"))
    )
    (net (code "6") (name "unconnected-(U102O-HDTXN0_D1CH0(RESERVED)-PadAK19)") (class "Default")
      (node (ref "U102") (pin "AK19") (pinfunction "HDTXN0_D1CH0(RESERVED)_AK19") (pintype "passive+no_connect"))
    )
    (net (code "7") (name "unconnected-(U102O-HDTXN0_D1CH1(RESERVED)-PadAK22)") (class "Default")
      (node (ref "U102") (pin "AK22") (pinfunction "HDTXN0_D1CH1(RESERVED)_AK22") (pintype "passive+no_connect"))
    )
    (net (code "8") (name "unconnected-(U102O-HDTXP0_D0CH0(RESERVED)-PadAK9)") (class "Default")
      (node (ref "U102") (pin "AK9") (pinfunction "HDTXP0_D0CH0(RESERVED)_AK9") (pintype "passive+no_connect"))
    )
    (net (code "9") (name "unconnected-(U102O-HDTXP0_D0CH1(RESERVED)-PadAK12)") (class "Default")
      (node (ref "U102") (pin "AK12") (pinfunction "HDTXP0_D0CH1(RESERVED)_AK12") (pintype "passive+no_connect"))
    )
    (net (code "10") (name "unconnected-(U102O-HDTXP0_D1CH0(RESERVED)-PadAK18)") (class "Default")
      (node (ref "U102") (pin "AK18") (pinfunction "HDTXP0_D1CH0(RESERVED)_AK18") (pintype "passive+no_connect"))
    )
    (net (code "11") (name "unconnected-(U102O-HDTXP0_D1CH1(RESERVED)-PadAK21)") (class "Default")
      (node (ref "U102") (pin "AK21") (pinfunction "HDTXP0_D1CH1(RESERVED)_AK21") (pintype "passive+no_connect"))
    )
    (net (code "12") (name "unconnected-(U102O-RESERVED-PadAK15)") (class "Default")
      (node (ref "U102") (pin "AK15") (pinfunction "RESERVED_AK15") (pintype "passive+no_connect"))
    )
    (net (code "13") (name "unconnected-(U102O-RESERVED-PadAK16)") (class "Default")
      (node (ref "U102") (pin "AK16") (pinfunction "RESERVED_AK16") (pintype "passive+no_connect"))
    )
    (net (code "14") (name "unconnected-(U102O-RESERVED-PadAK24)") (class "Default")
      (node (ref "U102") (pin "AK24") (pinfunction "RESERVED_AK24") (pintype "passive+no_connect"))
    )
    (net (code "15") (name "unconnected-(U102O-RESERVED-PadAK25)") (class "Default")
      (node (ref "U102") (pin "AK25") (pinfunction "RESERVED_AK25") (pintype "passive+no_connect"))
    )
    (net (code "16") (name "unconnected-(U102S-NC-PadAC4)") (class "Default")
      (node (ref "U102") (pin "AC4") (pinfunction "NC_AC4") (pintype "passive+no_connect"))
    )
    (net (code "17") (name "unconnected-(U102S-NC-PadAC29)") (class "Default")
      (node (ref "U102") (pin "AC29") (pinfunction "NC_AC29") (pintype "passive+no_connect"))
    )
    (net (code "18") (name "unconnected-(U102S-NC-PadAE7)") (class "Default")
      (node (ref "U102") (pin "AE7") (pinfunction "NC_AE7") (pintype "passive+no_connect"))
    )
    (net (code "19") (name "unconnected-(U102S-NC-PadAE26)") (class "Default")
      (node (ref "U102") (pin "AE26") (pinfunction "NC_AE26") (pintype "passive+no_connect"))
    )
    (net (code "20") (name "unconnected-(U102S-NC-PadAG2)") (class "Default")
      (node (ref "U102") (pin "AG2") (pinfunction "NC_AG2") (pintype "passive+no_connect"))
    )
    (net (code "21") (name "unconnected-(U102S-NC-PadAG24)") (class "Default")
      (node (ref "U102") (pin "AG24") (pinfunction "NC_AG24") (pintype "passive+no_connect"))
    )
    (net (code "22") (name "unconnected-(U102S-NC-PadAG31)") (class "Default")
      (node (ref "U102") (pin "AG31") (pinfunction "NC_AG31") (pintype "passive+no_connect"))
    )
    (net (code "23") (name "unconnected-(U102S-NC-PadE7)") (class "Default")
      (node (ref "U102") (pin "E7") (pinfunction "NC_E7") (pintype "passive+no_connect"))
    )
    (net (code "24") (name "unconnected-(U102S-NC-PadE26)") (class "Default")
      (node (ref "U102") (pin "E26") (pinfunction "NC_E26") (pintype "passive+no_connect"))
    )
    (net (code "25") (name "unconnected-(U102S-NC-PadG9)") (class "Default")
      (node (ref "U102") (pin "G9") (pinfunction "NC_G9") (pintype "passive+no_connect"))
    )
    (net (code "26") (name "unconnected-(U102S-NC-PadG10)") (class "Default")
      (node (ref "U102") (pin "G10") (pinfunction "NC_G10") (pintype "passive+no_connect"))
    )
    (net (code "27") (name "unconnected-(U102S-NC-PadG11)") (class "Default")
      (node (ref "U102") (pin "G11") (pinfunction "NC_G11") (pintype "passive+no_connect"))
    )
    (net (code "28") (name "unconnected-(U102S-NC-PadG14)") (class "Default")
      (node (ref "U102") (pin "G14") (pinfunction "NC_G14") (pintype "passive+no_connect"))
    )
    (net (code "29") (name "unconnected-(U102S-NC-PadG15)") (class "Default")
      (node (ref "U102") (pin "G15") (pinfunction "NC_G15") (pintype "passive+no_connect"))
    )
    (net (code "30") (name "unconnected-(U102S-NC-PadG16)") (class "Default")
      (node (ref "U102") (pin "G16") (pinfunction "NC_G16") (pintype "passive+no_connect"))
    )
    (net (code "31") (name "unconnected-(U102S-NC-PadG17)") (class "Default")
      (node (ref "U102") (pin "G17") (pinfunction "NC_G17") (pintype "passive+no_connect"))
    )
    (net (code "32") (name "unconnected-(U102S-NC-PadG18)") (class "Default")
      (node (ref "U102") (pin "G18") (pinfunction "NC_G18") (pintype "passive+no_connect"))
    )
    (net (code "33") (name "unconnected-(U102S-NC-PadG19)") (class "Default")
      (node (ref "U102") (pin "G19") (pinfunction "NC_G19") (pintype "passive+no_connect"))
    )
    (net (code "34") (name "unconnected-(U102S-NC-PadG22)") (class "Default")
      (node (ref "U102") (pin "G22") (pinfunction "NC_G22") (pintype "passive+no_connect"))
    )
    (net (code "35") (name "unconnected-(U102S-NC-PadG23)") (class "Default")
      (node (ref "U102") (pin "G23") (pinfunction "NC_G23") (pintype "passive+no_connect"))
    )
    (net (code "36") (name "unconnected-(U102S-NC-PadG24)") (class "Default")
      (node (ref "U102") (pin "G24") (pinfunction "NC_G24") (pintype "passive+no_connect"))
    )
    (net (code "37") (name "unconnected-(U102S-NC-PadH4)") (class "Default")
      (node (ref "U102") (pin "H4") (pinfunction "NC_H4") (pintype "passive+no_connect"))
    )
    (net (code "38") (name "unconnected-(U102S-NC-PadH29)") (class "Default")
      (node (ref "U102") (pin "H29") (pinfunction "NC_H29") (pintype "passive+no_connect"))
    )
    (net (code "39") (name "unconnected-(U102S-NC-PadL5)") (class "Default")
      (node (ref "U102") (pin "L5") (pinfunction "NC_L5") (pintype "passive+no_connect"))
    )
    (net (code "40") (name "unconnected-(U102S-NC-PadL28)") (class "Default")
      (node (ref "U102") (pin "L28") (pinfunction "NC_L28") (pintype "passive+no_connect"))
    )
    (net (code "41") (name "unconnected-(U102S-NC-PadV3)") (class "Default")
      (node (ref "U102") (pin "V3") (pinfunction "NC_V3") (pintype "passive+no_connect"))
    )
    (net (code "42") (name "unconnected-(U102S-NC-PadV30)") (class "Default")
      (node (ref "U102") (pin "V30") (pinfunction "NC_V30") (pintype "passive+no_connect"))
    )
    (net (code "43") (name "unconnected-(U102S-NC-PadW6)") (class "Default")
      (node (ref "U102") (pin "W6") (pinfunction "NC_W6") (pintype "passive+no_connect"))
    )
    (net (code "44") (name "unconnected-(U102S-NC-PadW27)") (class "Default")
      (node (ref "U102") (pin "W27") (pinfunction "NC_W27") (pintype "passive+no_connect"))
    )
  )
)
